# sensorCR123Orig.net
KiCad netlist of a schematic drawn in EAGLE
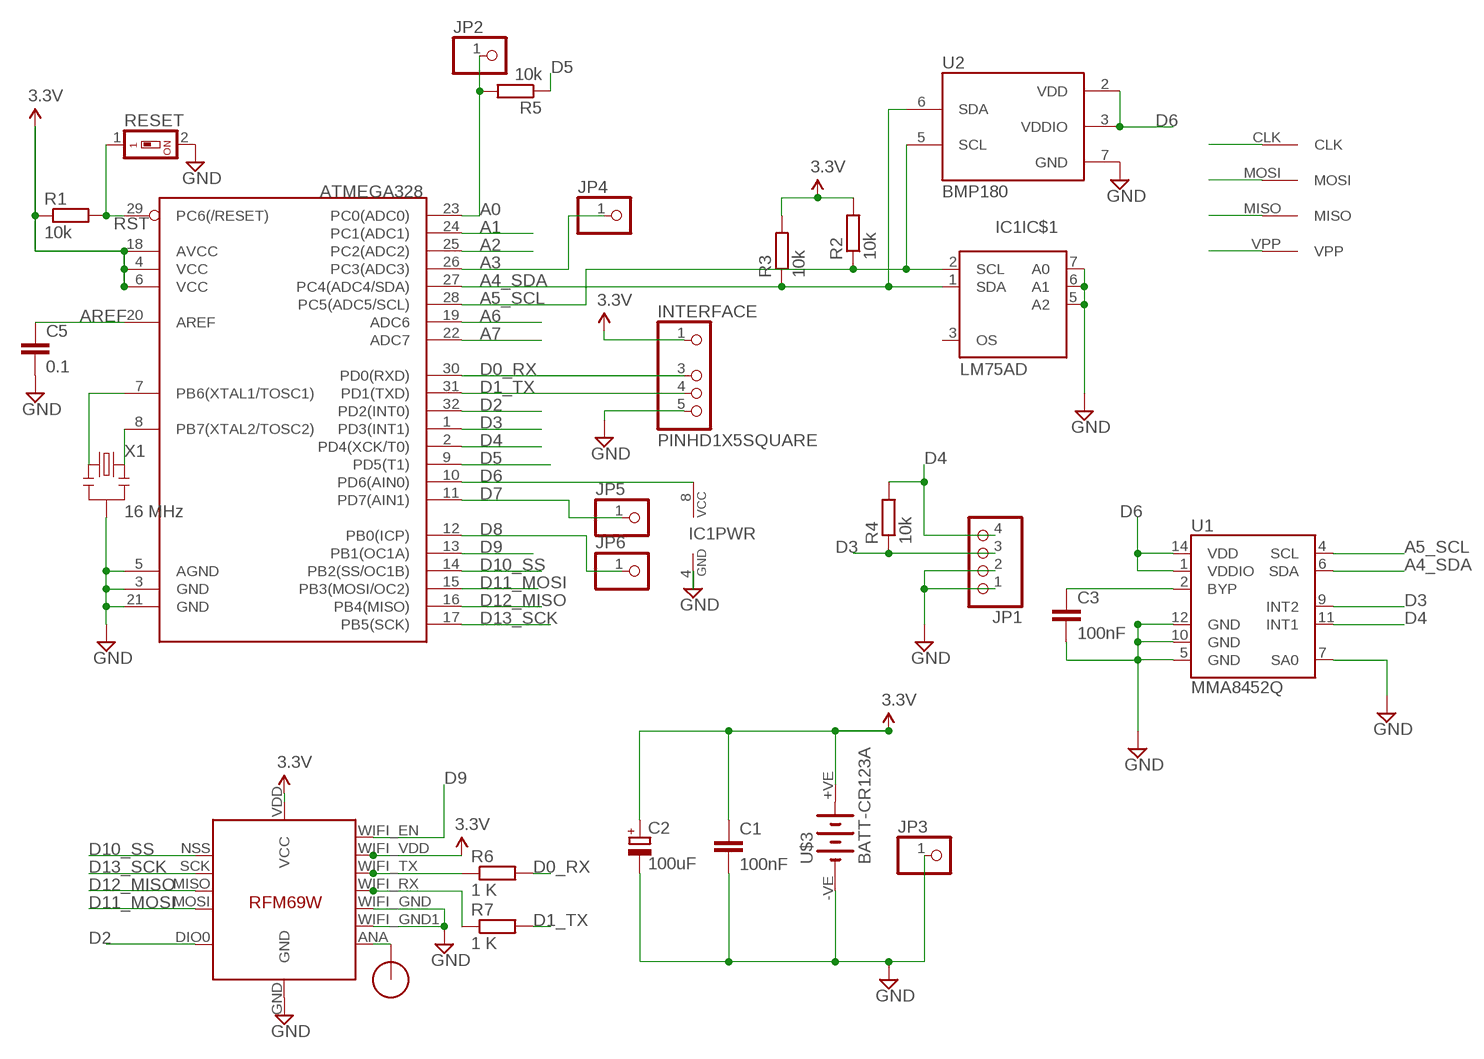
[diagram p0: schematic, sheet 1]

(export (version "E")
  (design (tool "Eeschema 10.0.6"))
  (components
    (comp (ref "ATMEGA328")
      (value "ATMega-328")
      (footprint "eagle-import:TQFP32-08")
      (libsource (lib "eagle-import") (part "ATMEGA168/328TQFP32"))
    )
    (comp (ref "C1")
      (value "100nF")
      (footprint "eagle-import:C2012")
      (libsource (lib "eagle-import") (part "C-EUC2012"))
    )
    (comp (ref "C2")
      (value "100uF")
      (footprint "eagle-import:SMC_B")
      (libsource (lib "eagle-import") (part "CPOL-EUSMCB"))
    )
    (comp (ref "C3")
      (value "100nF")
      (footprint "eagle-import:C2012")
      (libsource (lib "eagle-import") (part "C-EUC2012"))
    )
    (comp (ref "C5")
      (value "0.1")
      (footprint "eagle-import:C2012")
      (libsource (lib "eagle-import") (part "C-EUC2012"))
    )
    (comp (ref "IC1")
      (value "LM75AD")
      (footprint "eagle-import:SO08")
      (libsource (lib "eagle-import") (part "LM75AD"))
    )
    (comp (ref "IC4")
      (value "RFM69-ESP03")
      (footprint "eagle-import:RFM69W-ESP03")
      (libsource (lib "eagle-import") (part "RFM69-ESP03"))
    )
    (comp (ref "INTERFACE")
      (value "PINHD1X5SQUARE")
      (footprint "eagle-import:PINHD1X05-SQUARE")
      (libsource (lib "eagle-import") (part "PINHD1X5SQUARE"))
    )
    (comp (ref "JP1")
      (value "PINHD-1X04_2.54-S")
      (footprint "eagle-import:1X04-S")
      (libsource (lib "eagle-import") (part "PINHD-1X04_2.54-S"))
    )
    (comp (ref "JP2")
      (value "PINHD-1X01_2.54")
      (footprint "eagle-import:1X01")
      (libsource (lib "eagle-import") (part "PINHD-1X01_2.54"))
    )
    (comp (ref "JP3")
      (value "PINHD-1X01_2.54")
      (footprint "eagle-import:1X01")
      (libsource (lib "eagle-import") (part "PINHD-1X01_2.54"))
    )
    (comp (ref "JP4")
      (value "PINHD-1X01_2.54")
      (footprint "eagle-import:1X01")
      (libsource (lib "eagle-import") (part "PINHD-1X01_2.54"))
    )
    (comp (ref "JP5")
      (value "PINHD-1X01_2.54")
      (footprint "eagle-import:1X01")
      (libsource (lib "eagle-import") (part "PINHD-1X01_2.54"))
    )
    (comp (ref "JP6")
      (value "PINHD-1X01_2.54")
      (footprint "eagle-import:1X01")
      (libsource (lib "eagle-import") (part "PINHD-1X01_2.54"))
    )
    (comp (ref "R1")
      (value "10k")
      (footprint "eagle-import:R2012")
      (libsource (lib "eagle-import") (part "R-EU_R2012"))
    )
    (comp (ref "R2")
      (value "10k")
      (footprint "eagle-import:R2012")
      (libsource (lib "eagle-import") (part "R-EU_R2012"))
    )
    (comp (ref "R3")
      (value "10k")
      (footprint "eagle-import:R2012")
      (libsource (lib "eagle-import") (part "R-EU_R2012"))
    )
    (comp (ref "R4")
      (value "10k")
      (footprint "eagle-import:R2012")
      (libsource (lib "eagle-import") (part "R-EU_R2012"))
    )
    (comp (ref "R5")
      (value "10k")
      (footprint "eagle-import:R2012")
      (libsource (lib "eagle-import") (part "R-EU_R2012"))
    )
    (comp (ref "R6")
      (value "1 K")
      (footprint "eagle-import:M2012")
      (libsource (lib "eagle-import") (part "R-EU_M2012"))
    )
    (comp (ref "R7")
      (value "1 K")
      (footprint "eagle-import:M2012")
      (libsource (lib "eagle-import") (part "R-EU_M2012"))
    )
    (comp (ref "RESET")
      (value "SWS001")
      (footprint "eagle-import:SMS-001")
      (libsource (lib "eagle-import") (part "SWS001"))
    )
    (comp (ref "U$1")
      (value "RFM12B_ANTENNA")
      (footprint "eagle-import:RFM12B-ANTENNA")
      (libsource (lib "eagle-import") (part "RFM12B_ANTENNA"))
    )
    (comp (ref "U$2")
      (value "AVRHEADERDIP")
      (footprint "eagle-import:AVRHEADER")
      (libsource (lib "eagle-import") (part "AVRHEADERDIP"))
    )
    (comp (ref "U$3")
      (value "BATT-CR123A")
      (footprint "eagle-import:KEYSTONE-2_3A")
      (libsource (lib "eagle-import") (part "BATT-CR123A"))
    )
    (comp (ref "U1")
      (value "MMA8452Q")
      (footprint "eagle-import:QFN-16_0.5MM")
      (libsource (lib "eagle-import") (part "MMA8452Q"))
    )
    (comp (ref "U2")
      (value "BMP180")
      (footprint "eagle-import:BMP180")
      (libsource (lib "eagle-import") (part "BMP180"))
    )
    (comp (ref "X1")
      (value "16 MHz")
      (footprint "eagle-import:RESONATOR-SMD")
      (libsource (lib "eagle-import") (part "RESONATORSMD"))
    )
  )
  (nets
    (net (code "1") (name "/A0") (class "Default")
      (node (ref "ATMEGA328") (pin "23") (pinfunction "PC0(ADC0)_23") (pintype "bidirectional"))
      (node (ref "JP2") (pin "1") (pinfunction "1_1") (pintype "passive"))
      (node (ref "R5") (pin "2") (pinfunction "2_2") (pintype "passive"))
    )
    (net (code "2") (name "/A1") (class "Default")
      (node (ref "ATMEGA328") (pin "24") (pinfunction "PC1(ADC1)_24") (pintype "bidirectional"))
    )
    (net (code "3") (name "/A2") (class "Default")
      (node (ref "ATMEGA328") (pin "25") (pinfunction "PC2(ADC2)_25") (pintype "bidirectional"))
    )
    (net (code "4") (name "/A3") (class "Default")
      (node (ref "ATMEGA328") (pin "26") (pinfunction "PC3(ADC3)_26") (pintype "bidirectional"))
      (node (ref "JP4") (pin "1") (pinfunction "1_1") (pintype "passive"))
    )
    (net (code "5") (name "/A4_SDA") (class "Default")
      (node (ref "ATMEGA328") (pin "27") (pinfunction "PC4(ADC4/SDA)_27") (pintype "bidirectional"))
      (node (ref "IC1") (pin "1") (pinfunction "SDA_1") (pintype "bidirectional"))
      (node (ref "R3") (pin "1") (pinfunction "1_1") (pintype "passive"))
      (node (ref "U1") (pin "6") (pinfunction "SDA_6") (pintype "bidirectional"))
      (node (ref "U2") (pin "6") (pinfunction "SDA_6") (pintype "bidirectional"))
    )
    (net (code "6") (name "/A5_SCL") (class "Default")
      (node (ref "ATMEGA328") (pin "28") (pinfunction "PC5(ADC5/SCL)_28") (pintype "bidirectional"))
      (node (ref "IC1") (pin "2") (pinfunction "SCL_2") (pintype "input"))
      (node (ref "R2") (pin "1") (pinfunction "1_1") (pintype "passive"))
      (node (ref "U1") (pin "4") (pinfunction "SCL_4") (pintype "bidirectional"))
      (node (ref "U2") (pin "5") (pinfunction "SCL_5") (pintype "input"))
    )
    (net (code "7") (name "/A6") (class "Default")
      (node (ref "ATMEGA328") (pin "19") (pinfunction "ADC6_19") (pintype "bidirectional"))
    )
    (net (code "8") (name "/A7") (class "Default")
      (node (ref "ATMEGA328") (pin "22") (pinfunction "ADC7_22") (pintype "bidirectional"))
    )
    (net (code "9") (name "/AREF") (class "Default")
      (node (ref "ATMEGA328") (pin "20") (pinfunction "AREF_20") (pintype "bidirectional"))
      (node (ref "C5") (pin "1") (pinfunction "1_1") (pintype "passive"))
    )
    (net (code "10") (name "/D0_RX") (class "Default")
      (node (ref "ATMEGA328") (pin "30") (pinfunction "PD0(RXD)_30") (pintype "bidirectional"))
      (node (ref "INTERFACE") (pin "3") (pinfunction "3_3") (pintype "passive"))
      (node (ref "R6") (pin "2") (pinfunction "2_2") (pintype "passive"))
    )
    (net (code "11") (name "/D1_TX") (class "Default")
      (node (ref "ATMEGA328") (pin "31") (pinfunction "PD1(TXD)_31") (pintype "bidirectional"))
      (node (ref "INTERFACE") (pin "4") (pinfunction "4_4") (pintype "passive"))
      (node (ref "R7") (pin "2") (pinfunction "2_2") (pintype "passive"))
    )
    (net (code "12") (name "/D2") (class "Default")
      (node (ref "ATMEGA328") (pin "32") (pinfunction "PD2(INT0)_32") (pintype "bidirectional"))
      (node (ref "IC4") (pin "DIO0") (pinfunction "DIO0_DIO0") (pintype "open_collector"))
    )
    (net (code "13") (name "/D3") (class "Default")
      (node (ref "ATMEGA328") (pin "1") (pinfunction "PD3(INT1)_1") (pintype "bidirectional"))
      (node (ref "JP1") (pin "3") (pinfunction "3_3") (pintype "passive"))
      (node (ref "R4") (pin "1") (pinfunction "1_1") (pintype "passive"))
      (node (ref "U1") (pin "9") (pinfunction "INT2_9") (pintype "bidirectional"))
    )
    (net (code "14") (name "/D4") (class "Default")
      (node (ref "ATMEGA328") (pin "2") (pinfunction "PD4(XCK/T0)_2") (pintype "bidirectional"))
      (node (ref "JP1") (pin "4") (pinfunction "4_4") (pintype "passive"))
      (node (ref "R4") (pin "2") (pinfunction "2_2") (pintype "passive"))
      (node (ref "U1") (pin "11") (pinfunction "INT1_11") (pintype "bidirectional"))
    )
    (net (code "15") (name "/D5") (class "Default")
      (node (ref "ATMEGA328") (pin "9") (pinfunction "PD5(T1)_9") (pintype "bidirectional"))
      (node (ref "R5") (pin "1") (pinfunction "1_1") (pintype "passive"))
    )
    (net (code "16") (name "/D6") (class "Default")
      (node (ref "ATMEGA328") (pin "10") (pinfunction "PD6(AIN0)_10") (pintype "bidirectional"))
      (node (ref "IC1") (pin "8") (pinfunction "VCC_8") (pintype "power_in"))
      (node (ref "U1") (pin "1") (pinfunction "VDDIO_1") (pintype "bidirectional"))
      (node (ref "U1") (pin "14") (pinfunction "VDD_14") (pintype "bidirectional"))
      (node (ref "U2") (pin "2") (pinfunction "VDD_2") (pintype "power_in"))
      (node (ref "U2") (pin "3") (pinfunction "VDDIO_3") (pintype "power_in"))
    )
    (net (code "17") (name "/D7") (class "Default")
      (node (ref "ATMEGA328") (pin "11") (pinfunction "PD7(AIN1)_11") (pintype "bidirectional"))
      (node (ref "JP5") (pin "1") (pinfunction "1_1") (pintype "passive"))
    )
    (net (code "18") (name "/D8") (class "Default")
      (node (ref "ATMEGA328") (pin "12") (pinfunction "PB0(ICP)_12") (pintype "bidirectional"))
      (node (ref "JP6") (pin "1") (pinfunction "1_1") (pintype "passive"))
    )
    (net (code "19") (name "/D9") (class "Default")
      (node (ref "ATMEGA328") (pin "13") (pinfunction "PB1(OC1A)_13") (pintype "bidirectional"))
      (node (ref "IC4") (pin "WIFI_EN") (pinfunction "WIFI_EN_WIFI_EN") (pintype "input"))
    )
    (net (code "20") (name "/D10_SS") (class "Default")
      (node (ref "ATMEGA328") (pin "14") (pinfunction "PB2(SS/OC1B)_14") (pintype "bidirectional"))
      (node (ref "IC4") (pin "NSS") (pinfunction "SEL_NSS") (pintype "input"))
    )
    (net (code "21") (name "/D11_MOSI") (class "Default")
      (node (ref "ATMEGA328") (pin "15") (pinfunction "PB3(MOSI/OC2)_15") (pintype "bidirectional"))
      (node (ref "IC4") (pin "MOSI") (pinfunction "MOSI_MOSI") (pintype "output"))
      (node (ref "U$2") (pin "MOSI") (pinfunction "MOSI_MOSI") (pintype "bidirectional"))
    )
    (net (code "22") (name "/D12_MISO") (class "Default")
      (node (ref "ATMEGA328") (pin "16") (pinfunction "PB4(MISO)_16") (pintype "bidirectional"))
      (node (ref "IC4") (pin "MISO") (pinfunction "MISO_MISO") (pintype "input"))
      (node (ref "U$2") (pin "MISO") (pinfunction "MISO_MISO") (pintype "bidirectional"))
    )
    (net (code "23") (name "/D13_SCK") (class "Default")
      (node (ref "ATMEGA328") (pin "17") (pinfunction "PB5(SCK)_17") (pintype "bidirectional"))
      (node (ref "IC4") (pin "SCK") (pinfunction "SCK_SCK") (pintype "input"))
      (node (ref "U$2") (pin "CLK") (pinfunction "CLK_CLK") (pintype "bidirectional"))
    )
    (net (code "24") (name "/RST") (class "Default")
      (node (ref "ATMEGA328") (pin "29") (pinfunction "PC6(/RESET)_29") (pintype "bidirectional"))
      (node (ref "R1") (pin "2") (pinfunction "2_2") (pintype "passive"))
      (node (ref "RESET") (pin "1") (pinfunction "1_1") (pintype "passive"))
      (node (ref "U$2") (pin "VPP") (pinfunction "VPP_VPP") (pintype "bidirectional"))
    )
    (net (code "25") (name "3.3V") (class "Default")
      (node (ref "ATMEGA328") (pin "18") (pinfunction "AVCC_18") (pintype "bidirectional"))
      (node (ref "ATMEGA328") (pin "4") (pinfunction "VCC_4") (pintype "bidirectional"))
      (node (ref "ATMEGA328") (pin "6") (pinfunction "VCC_6") (pintype "bidirectional"))
      (node (ref "C1") (pin "1") (pinfunction "1_1") (pintype "passive"))
      (node (ref "C2") (pin "+") (pinfunction "+_+") (pintype "passive"))
      (node (ref "IC4") (pin "VDD") (pinfunction "VCC_VDD") (pintype "power_in"))
      (node (ref "IC4") (pin "WIFI_VDD") (pinfunction "WIFI_VDD_WIFI_VDD") (pintype "input"))
      (node (ref "INTERFACE") (pin "1") (pinfunction "1_1") (pintype "passive"))
      (node (ref "R1") (pin "1") (pinfunction "1_1") (pintype "passive"))
      (node (ref "R2") (pin "2") (pinfunction "2_2") (pintype "passive"))
      (node (ref "R3") (pin "2") (pinfunction "2_2") (pintype "passive"))
      (node (ref "U$3") (pin "+VE") (pinfunction "+_+VE") (pintype "passive"))
    )
    (net (code "26") (name "GND") (class "Default")
      (node (ref "ATMEGA328") (pin "21") (pinfunction "GND_21") (pintype "bidirectional"))
      (node (ref "ATMEGA328") (pin "3") (pinfunction "GND_3") (pintype "bidirectional"))
      (node (ref "ATMEGA328") (pin "5") (pinfunction "AGND_5") (pintype "bidirectional"))
      (node (ref "C1") (pin "2") (pinfunction "2_2") (pintype "passive"))
      (node (ref "C2") (pin "-") (pinfunction "-_-") (pintype "passive"))
      (node (ref "C3") (pin "2") (pinfunction "2_2") (pintype "passive"))
      (node (ref "C5") (pin "2") (pinfunction "2_2") (pintype "passive"))
      (node (ref "IC1") (pin "4") (pinfunction "GND_4") (pintype "power_in"))
      (node (ref "IC1") (pin "5") (pinfunction "A2_5") (pintype "input"))
      (node (ref "IC1") (pin "6") (pinfunction "A1_6") (pintype "input"))
      (node (ref "IC1") (pin "7") (pinfunction "A0_7") (pintype "input"))
      (node (ref "IC4") (pin "GND") (pinfunction "GND_GND") (pintype "power_in"))
      (node (ref "IC4") (pin "WIFI_GND") (pinfunction "WIFI_GND_WIFI_GND") (pintype "input"))
      (node (ref "IC4") (pin "WIFI_GND1") (pinfunction "WIFI_GND1_WIFI_GND1") (pintype "input"))
      (node (ref "INTERFACE") (pin "5") (pinfunction "5_5") (pintype "passive"))
      (node (ref "JP1") (pin "1") (pinfunction "1_1") (pintype "passive"))
      (node (ref "JP1") (pin "2") (pinfunction "2_2") (pintype "passive"))
      (node (ref "JP3") (pin "1") (pinfunction "1_1") (pintype "passive"))
      (node (ref "RESET") (pin "2") (pinfunction "2_2") (pintype "passive"))
      (node (ref "U$3") (pin "-VE") (pinfunction "-_-VE") (pintype "passive"))
      (node (ref "U1") (pin "10") (pinfunction "GND_10") (pintype "bidirectional"))
      (node (ref "U1") (pin "12") (pinfunction "GND_12") (pintype "bidirectional"))
      (node (ref "U1") (pin "5") (pinfunction "GND_5") (pintype "bidirectional"))
      (node (ref "U1") (pin "7") (pinfunction "SA0_7") (pintype "bidirectional"))
      (node (ref "U2") (pin "7") (pinfunction "GND_7") (pintype "power_in"))
      (node (ref "X1") (pin "2") (pinfunction "2_2") (pintype "passive"))
    )
    (net (code "27") (name "Net-(ATMEGA328-PB6(XTAL1{slash}TOSC1))") (class "Default")
      (node (ref "ATMEGA328") (pin "7") (pinfunction "PB6(XTAL1/TOSC1)_7") (pintype "bidirectional"))
      (node (ref "X1") (pin "1") (pinfunction "1_1") (pintype "passive"))
    )
    (net (code "28") (name "Net-(ATMEGA328-PB7(XTAL2{slash}TOSC2))") (class "Default")
      (node (ref "ATMEGA328") (pin "8") (pinfunction "PB7(XTAL2/TOSC2)_8") (pintype "bidirectional"))
      (node (ref "X1") (pin "3") (pinfunction "3_3") (pintype "passive"))
    )
    (net (code "29") (name "Net-(IC4-ANT)") (class "Default")
      (node (ref "IC4") (pin "ANA") (pinfunction "ANT_ANA") (pintype "passive"))
      (node (ref "U$1") (pin "P$1") (pinfunction "1_P$1") (pintype "bidirectional"))
    )
    (net (code "30") (name "Net-(IC4-PadWIFI_RX)") (class "Default")
      (node (ref "IC4") (pin "WIFI_RX") (pinfunction "WIFI_RX_WIFI_RX") (pintype "input"))
      (node (ref "R7") (pin "1") (pinfunction "1_1") (pintype "passive"))
    )
    (net (code "31") (name "Net-(IC4-PadWIFI_TX)") (class "Default")
      (node (ref "IC4") (pin "WIFI_TX") (pinfunction "WIFI_TX_WIFI_TX") (pintype "input"))
      (node (ref "R6") (pin "1") (pinfunction "1_1") (pintype "passive"))
    )
    (net (code "32") (name "Net-(U1-BYP)") (class "Default")
      (node (ref "C3") (pin "1") (pinfunction "1_1") (pintype "passive"))
      (node (ref "U1") (pin "2") (pinfunction "BYP_2") (pintype "bidirectional"))
    )
    (net (code "33") (name "unconnected-(IC1A-OS-Pad3)") (class "Default")
      (node (ref "IC1") (pin "3") (pinfunction "OS_3") (pintype "output"))
    )
  )
)
